# uC.net
KiCad netlist of a schematic drawn in Altium Designer
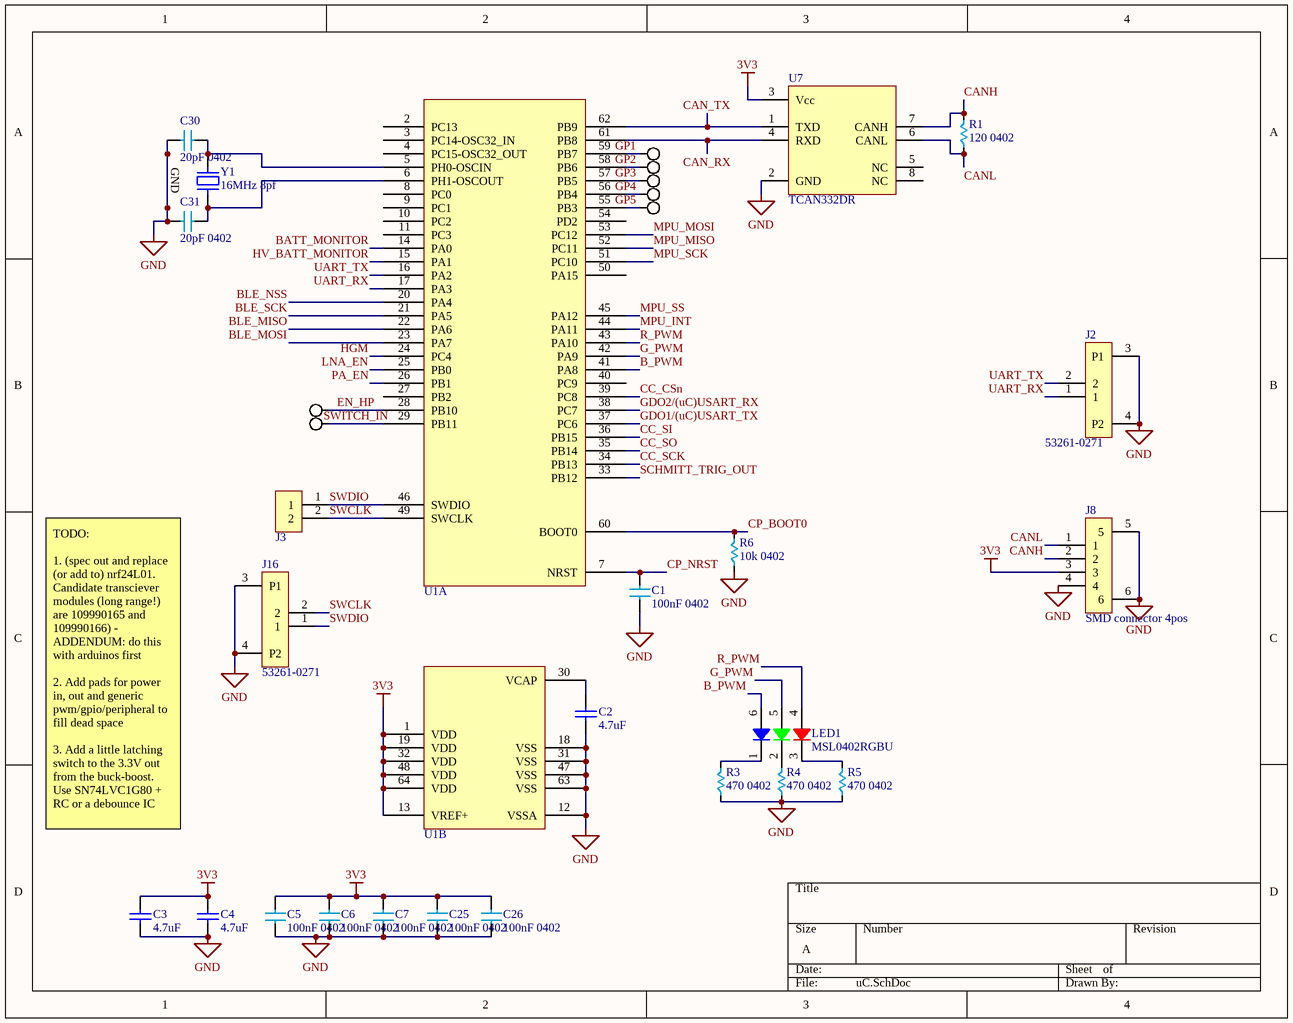
[diagram p0: uC.SchDoc]

(export (version "E")
  (design (tool "Eeschema 10.0.6"))
  (components
    (comp (ref "C1") (value "100nF 0402") (footprint "C0402") (libsource (lib "RLC") (part "C0402-100nF")))
    (comp (ref "C2")
      (value "4.7uF")
      (footprint "C0603")
      (description "4.7uF 0603")
      (fields
        (field (name "MANUFACTURER") "Samsung")
        (field (name "MANUFACTURER PART NUMBER") "CL05F104ZO5NNNC")
        (field (name "PUBLISHER") "Altium Limited")
      )
      (libsource (lib "robot-cortex") (part "C-4.7uF-0603"))
    )
    (comp (ref "C3")
      (value "4.7uF")
      (footprint "C0603")
      (description "4.7uF 0603")
      (fields
        (field (name "MANUFACTURER") "Samsung")
        (field (name "MANUFACTURER PART NUMBER") "CL05F104ZO5NNNC")
        (field (name "PUBLISHER") "Altium Limited")
      )
      (libsource (lib "robot-cortex") (part "C-4.7uF-0603"))
    )
    (comp (ref "C4")
      (value "4.7uF")
      (footprint "C0603")
      (description "4.7uF 0603")
      (fields
        (field (name "MANUFACTURER") "Samsung")
        (field (name "MANUFACTURER PART NUMBER") "CL05F104ZO5NNNC")
        (field (name "PUBLISHER") "Altium Limited")
      )
      (libsource (lib "robot-cortex") (part "C-4.7uF-0603"))
    )
    (comp (ref "C5") (value "100nF 0402") (footprint "C0402") (libsource (lib "RLC") (part "C0402-100nF")))
    (comp (ref "C6") (value "100nF 0402") (footprint "C0402") (libsource (lib "RLC") (part "C0402-100nF")))
    (comp (ref "C7") (value "100nF 0402") (footprint "C0402") (libsource (lib "RLC") (part "C0402-100nF")))
    (comp (ref "C25") (value "100nF 0402") (footprint "C0402") (libsource (lib "RLC") (part "C0402-100nF")))
    (comp (ref "C26") (value "100nF 0402") (footprint "C0402") (libsource (lib "RLC") (part "C0402-100nF")))
    (comp (ref "C30") (value "20pF 0402") (footprint "C0402") (libsource (lib "RLC") (part "C0402-20pF")))
    (comp (ref "C31") (value "20pF 0402") (footprint "C0402") (libsource (lib "RLC") (part "C0402-20pF")))
    (comp (ref "J2")
      (value "53261-0271")
      (footprint "0532610271")
      (description "Headers & Wire Housings 1.25MM HDR 2 CKT Right-Angle")
      (fields (field (name "MANUFACTURER") "Molex"))
      (libsource (lib "robot-cortex") (part "53261-0271"))
    )
    (comp (ref "J3")
      (value "Header 2")
      (footprint "DUAL_PADS")
      (libsource (lib "robot-cortex") (part "DUAL_PADS"))
    )
    (comp (ref "J5")
      (value "PAD-SINGLE")
      (footprint "PAD-SINGLE")
      (description "Single Thru Hole Pad")
      (libsource (lib "robot-cortex") (part "PAD-SINGLE"))
    )
    (comp (ref "J6")
      (value "PAD-SINGLE")
      (footprint "PAD-SINGLE")
      (description "Single Thru Hole Pad")
      (libsource (lib "robot-cortex") (part "PAD-SINGLE"))
    )
    (comp (ref "J8")
      (value "SMD connector 4pos")
      (footprint "0532610471")
      (description "Headers & Wire Housings 1.25MM HDR 4 CKT Right-Angle")
      (fields (field (name "MANUFACTURER") "Molex"))
      (libsource (lib "robot-cortex") (part "0532610471"))
    )
    (comp (ref "J9")
      (value "PAD-SINGLE")
      (footprint "PAD-SINGLE")
      (description "Single Thru Hole Pad")
      (libsource (lib "robot-cortex") (part "PAD-SINGLE"))
    )
    (comp (ref "J10")
      (value "PAD-SINGLE")
      (footprint "PAD-SINGLE")
      (description "Single Thru Hole Pad")
      (libsource (lib "robot-cortex") (part "PAD-SINGLE"))
    )
    (comp (ref "J11")
      (value "PAD-SINGLE")
      (footprint "PAD-SINGLE")
      (description "Single Thru Hole Pad")
      (libsource (lib "robot-cortex") (part "PAD-SINGLE"))
    )
    (comp (ref "J12")
      (value "PAD-SINGLE")
      (footprint "PAD-SINGLE")
      (description "Single Thru Hole Pad")
      (libsource (lib "robot-cortex") (part "PAD-SINGLE"))
    )
    (comp (ref "J13")
      (value "PAD-SINGLE")
      (footprint "PAD-SINGLE")
      (description "Single Thru Hole Pad")
      (libsource (lib "robot-cortex") (part "PAD-SINGLE"))
    )
    (comp (ref "J16")
      (value "53261-0271")
      (footprint "533980271")
      (description "Headers & Wire Housings 1.25MM HDR 2 CKT Right-Angle")
      (fields (field (name "MANUFACTURER") "Molex"))
      (libsource (lib "") (part "53261-0271_1"))
    )
    (comp (ref "LED1")
      (value "MSL0402RGBU")
      (footprint "MSL0402RGBU")
      (fields (field (name "MANUFACTURER") "Rohm") (field (name "MANUFACTURER PART NUMBER") "MSL0402RGBU1"))
      (libsource (lib "robot-cortex") (part "MSL0402RGBU"))
    )
    (comp (ref "R1")
      (value "120 0402")
      (footprint "R0402")
      (description "120 Ohm 0402")
      (libsource (lib "robot-cortex") (part "R-120-0402"))
    )
    (comp (ref "R3")
      (value "470 0402")
      (footprint "R0402")
      (fields
        (field (name "MANUFACTURER") "Yageo")
        (field (name "MANUFACTURER PART NUMBER") "RC0402JR-07470RL")
        (field (name "TOLERANCE") "5%")
      )
      (libsource (lib "robot-cortex") (part "R-470-0402"))
    )
    (comp (ref "R4")
      (value "470 0402")
      (footprint "R0402")
      (fields
        (field (name "MANUFACTURER") "Yageo")
        (field (name "MANUFACTURER PART NUMBER") "RC0402JR-07470RL")
        (field (name "TOLERANCE") "5%")
      )
      (libsource (lib "robot-cortex") (part "R-470-0402"))
    )
    (comp (ref "R5")
      (value "470 0402")
      (footprint "R0402")
      (fields
        (field (name "MANUFACTURER") "Yageo")
        (field (name "MANUFACTURER PART NUMBER") "RC0402JR-07470RL")
        (field (name "TOLERANCE") "5%")
      )
      (libsource (lib "robot-cortex") (part "R-470-0402"))
    )
    (comp (ref "R6") (value "10k 0402") (footprint "R0402") (libsource (lib "RLC") (part "R-10k-0402")))
    (comp (ref "U1")
      (value "STM32F730R8T6")
      (footprint "QFP-64")
      (libsource (lib "robot-cortex") (part "STM32F730R8T6"))
    )
    (comp (ref "U7")
      (value "TCAN332DR")
      (footprint "robot-cortex:SOIC8-D0008A")
      (fields (field (name "MANUFACTURER") "Texas Instruments"))
      (libsource (lib "robot-cortex") (part "TCAN332"))
    )
    (comp (ref "Y1")
      (value "16MHz 8pf")
      (footprint "robot-cortex:NDK NX3225GA")
      (description "SMT Crystal")
      (fields
        (field (name "MANUFACTURER") "NDK")
        (field (name "MANUFACTURER PART NUMBER") "NX3225SA-16.000000MHZ-T1")
      )
      (libsource (lib "robot-cortex") (part "NDK Crystal NX3225SA"))
    )
  )
  (nets
    (net (code "1") (name "/BATT_MONITOR") (class "Default")
      (node (ref "U1") (pin "14") (pinfunction "PA0_14") (pintype "passive"))
    )
    (net (code "2") (name "/BLE_MISO") (class "Default")
      (node (ref "U1") (pin "22") (pinfunction "PA6_22") (pintype "passive"))
    )
    (net (code "3") (name "/BLE_MOSI") (class "Default")
      (node (ref "U1") (pin "23") (pinfunction "PA7_23") (pintype "passive"))
    )
    (net (code "4") (name "/BLE_NSS") (class "Default")
      (node (ref "U1") (pin "20") (pinfunction "PA4_20") (pintype "passive"))
    )
    (net (code "5") (name "/BLE_SCK") (class "Default")
      (node (ref "U1") (pin "21") (pinfunction "PA5_21") (pintype "passive"))
    )
    (net (code "6") (name "/B_PWM") (class "Default")
      (node (ref "LED1") (pin "6") (pinfunction "6_6") (pintype "passive"))
      (node (ref "U1") (pin "41") (pinfunction "PA8_41") (pintype "passive"))
    )
    (net (code "7") (name "/CANH") (class "Default")
      (node (ref "J8") (pin "2") (pinfunction "2_2") (pintype "power_in"))
      (node (ref "R1") (pin "1") (pinfunction "1_1") (pintype "passive"))
      (node (ref "U7") (pin "7") (pinfunction "CANH_7") (pintype "power_in"))
    )
    (net (code "8") (name "/CANL") (class "Default")
      (node (ref "J8") (pin "1") (pinfunction "1_1") (pintype "power_in"))
      (node (ref "R1") (pin "2") (pinfunction "2_2") (pintype "passive"))
      (node (ref "U7") (pin "6") (pinfunction "CANL_6") (pintype "power_in"))
    )
    (net (code "9") (name "/CAN_RX") (class "Default")
      (node (ref "U1") (pin "61") (pinfunction "PB8_61") (pintype "passive"))
      (node (ref "U7") (pin "4") (pinfunction "RXD_4") (pintype "power_in"))
    )
    (net (code "10") (name "/CAN_TX") (class "Default")
      (node (ref "U1") (pin "62") (pinfunction "PB9_62") (pintype "passive"))
      (node (ref "U7") (pin "1") (pinfunction "TXD_1") (pintype "power_in"))
    )
    (net (code "11") (name "/CC_CSn") (class "Default")
      (node (ref "U1") (pin "39") (pinfunction "PC8_39") (pintype "passive"))
    )
    (net (code "12") (name "/CC_SCK") (class "Default")
      (node (ref "U1") (pin "34") (pinfunction "PB13_34") (pintype "passive"))
    )
    (net (code "13") (name "/CC_SI") (class "Default")
      (node (ref "U1") (pin "36") (pinfunction "PB15_36") (pintype "passive"))
    )
    (net (code "14") (name "/CC_SO") (class "Default")
      (node (ref "U1") (pin "35") (pinfunction "PB14_35") (pintype "passive"))
    )
    (net (code "15") (name "/CP_BOOT0") (class "Default")
      (node (ref "R6") (pin "1") (pinfunction "1_1") (pintype "passive"))
      (node (ref "U1") (pin "60") (pinfunction "BOOT0_60") (pintype "passive"))
    )
    (net (code "16") (name "/CP_NRST") (class "Default")
      (node (ref "C1") (pin "1") (pinfunction "1_1") (pintype "passive"))
      (node (ref "U1") (pin "7") (pinfunction "NRST_7") (pintype "passive"))
    )
    (net (code "17") (name "/EN_HP") (class "Default")
      (node (ref "J12") (pin "1") (pinfunction "1_1") (pintype "passive"))
      (node (ref "U1") (pin "28") (pinfunction "PB10_28") (pintype "passive"))
    )
    (net (code "18") (name "/GDO1{slash}(uC)USART_TX") (class "Default")
      (node (ref "U1") (pin "37") (pinfunction "PC6_37") (pintype "passive"))
    )
    (net (code "19") (name "/GDO2{slash}(uC)USART_RX") (class "Default")
      (node (ref "U1") (pin "38") (pinfunction "PC7_38") (pintype "passive"))
    )
    (net (code "20") (name "/GP1") (class "Default")
      (node (ref "J5") (pin "1") (pinfunction "1_1") (pintype "passive"))
      (node (ref "U1") (pin "59") (pinfunction "PB7_59") (pintype "passive"))
    )
    (net (code "21") (name "/GP2") (class "Default")
      (node (ref "J6") (pin "1") (pinfunction "1_1") (pintype "passive"))
      (node (ref "U1") (pin "58") (pinfunction "PB6_58") (pintype "passive"))
    )
    (net (code "22") (name "/GP3") (class "Default")
      (node (ref "J9") (pin "1") (pinfunction "1_1") (pintype "passive"))
      (node (ref "U1") (pin "57") (pinfunction "PB5_57") (pintype "passive"))
    )
    (net (code "23") (name "/GP4") (class "Default")
      (node (ref "J10") (pin "1") (pinfunction "1_1") (pintype "passive"))
      (node (ref "U1") (pin "56") (pinfunction "PB4_56") (pintype "passive"))
    )
    (net (code "24") (name "/GP5") (class "Default")
      (node (ref "J11") (pin "1") (pinfunction "1_1") (pintype "passive"))
      (node (ref "U1") (pin "55") (pinfunction "PB3_55") (pintype "passive"))
    )
    (net (code "25") (name "/G_PWM") (class "Default")
      (node (ref "LED1") (pin "5") (pinfunction "5_5") (pintype "passive"))
      (node (ref "U1") (pin "42") (pinfunction "PA9_42") (pintype "passive"))
    )
    (net (code "26") (name "/HGM") (class "Default")
      (node (ref "U1") (pin "24") (pinfunction "PC4_24") (pintype "passive"))
    )
    (net (code "27") (name "/HV_BATT_MONITOR") (class "Default")
      (node (ref "U1") (pin "15") (pinfunction "PA1_15") (pintype "passive"))
    )
    (net (code "28") (name "/LNA_EN") (class "Default")
      (node (ref "U1") (pin "25") (pinfunction "PB0_25") (pintype "passive"))
    )
    (net (code "29") (name "/MPU_INT") (class "Default")
      (node (ref "U1") (pin "44") (pinfunction "PA11_44") (pintype "passive"))
    )
    (net (code "30") (name "/MPU_MISO") (class "Default")
      (node (ref "U1") (pin "52") (pinfunction "PC11_52") (pintype "passive"))
    )
    (net (code "31") (name "/MPU_MOSI") (class "Default")
      (node (ref "U1") (pin "53") (pinfunction "PC12_53") (pintype "passive"))
    )
    (net (code "32") (name "/MPU_SCK") (class "Default")
      (node (ref "U1") (pin "51") (pinfunction "PC10_51") (pintype "passive"))
    )
    (net (code "33") (name "/MPU_SS") (class "Default")
      (node (ref "U1") (pin "45") (pinfunction "PA12_45") (pintype "passive"))
    )
    (net (code "34") (name "/PA_EN") (class "Default")
      (node (ref "U1") (pin "26") (pinfunction "PB1_26") (pintype "passive"))
    )
    (net (code "35") (name "/R_PWM") (class "Default")
      (node (ref "LED1") (pin "4") (pinfunction "4_4") (pintype "passive"))
      (node (ref "U1") (pin "43") (pinfunction "PA10_43") (pintype "passive"))
    )
    (net (code "36") (name "/SCHMITT_TRIG_OUT") (class "Default")
      (node (ref "U1") (pin "33") (pinfunction "PB12_33") (pintype "passive"))
    )
    (net (code "37") (name "/SWCLK") (class "Default")
      (node (ref "J16") (pin "2") (pinfunction "2_2") (pintype "power_in"))
      (node (ref "J3") (pin "2") (pinfunction "2_2") (pintype "power_in"))
      (node (ref "U1") (pin "49") (pinfunction "SWCLK_49") (pintype "passive"))
    )
    (net (code "38") (name "/SWDIO") (class "Default")
      (node (ref "J16") (pin "1") (pinfunction "1_1") (pintype "power_in"))
      (node (ref "J3") (pin "1") (pinfunction "1_1") (pintype "power_in"))
      (node (ref "U1") (pin "46") (pinfunction "SWDIO_46") (pintype "passive"))
    )
    (net (code "39") (name "/SWITCH_IN") (class "Default")
      (node (ref "J13") (pin "1") (pinfunction "1_1") (pintype "passive"))
      (node (ref "U1") (pin "29") (pinfunction "PB11_29") (pintype "passive"))
    )
    (net (code "40") (name "/UART_RX") (class "Default")
      (node (ref "J2") (pin "1") (pinfunction "1_1") (pintype "power_in"))
      (node (ref "U1") (pin "17") (pinfunction "PA3_17") (pintype "passive"))
    )
    (net (code "41") (name "/UART_TX") (class "Default")
      (node (ref "J2") (pin "2") (pinfunction "2_2") (pintype "power_in"))
      (node (ref "U1") (pin "16") (pinfunction "PA2_16") (pintype "passive"))
    )
    (net (code "42") (name "3V3") (class "Default")
      (node (ref "C25") (pin "1") (pinfunction "1_1") (pintype "passive"))
      (node (ref "C26") (pin "1") (pinfunction "1_1") (pintype "passive"))
      (node (ref "C3") (pin "2") (pinfunction "2_2") (pintype "passive"))
      (node (ref "C4") (pin "2") (pinfunction "2_2") (pintype "passive"))
      (node (ref "C5") (pin "1") (pinfunction "1_1") (pintype "passive"))
      (node (ref "C6") (pin "1") (pinfunction "1_1") (pintype "passive"))
      (node (ref "C7") (pin "1") (pinfunction "1_1") (pintype "passive"))
      (node (ref "J8") (pin "3") (pinfunction "3_3") (pintype "power_in"))
      (node (ref "U1") (pin "1") (pinfunction "VDD_1") (pintype "passive"))
      (node (ref "U1") (pin "13") (pinfunction "VREF+_13") (pintype "passive"))
      (node (ref "U1") (pin "19") (pinfunction "VDD_19") (pintype "passive"))
      (node (ref "U1") (pin "32") (pinfunction "VDD_32") (pintype "passive"))
      (node (ref "U1") (pin "48") (pinfunction "VDD_48") (pintype "passive"))
      (node (ref "U1") (pin "64") (pinfunction "VDD_64") (pintype "passive"))
      (node (ref "U7") (pin "3") (pinfunction "Vcc_3") (pintype "power_in"))
    )
    (net (code "43") (name "GND") (class "Default")
      (node (ref "C1") (pin "2") (pinfunction "2_2") (pintype "passive"))
      (node (ref "C2") (pin "1") (pinfunction "1_1") (pintype "passive"))
      (node (ref "C25") (pin "2") (pinfunction "2_2") (pintype "passive"))
      (node (ref "C26") (pin "2") (pinfunction "2_2") (pintype "passive"))
      (node (ref "C3") (pin "1") (pinfunction "1_1") (pintype "passive"))
      (node (ref "C30") (pin "2") (pinfunction "2_2") (pintype "passive"))
      (node (ref "C31") (pin "2") (pinfunction "2_2") (pintype "passive"))
      (node (ref "C4") (pin "1") (pinfunction "1_1") (pintype "passive"))
      (node (ref "C5") (pin "2") (pinfunction "2_2") (pintype "passive"))
      (node (ref "C6") (pin "2") (pinfunction "2_2") (pintype "passive"))
      (node (ref "C7") (pin "2") (pinfunction "2_2") (pintype "passive"))
      (node (ref "J16") (pin "3") (pinfunction "P1_3") (pintype "power_in"))
      (node (ref "J16") (pin "4") (pinfunction "P2_4") (pintype "power_in"))
      (node (ref "J2") (pin "3") (pinfunction "P1_3") (pintype "power_in"))
      (node (ref "J2") (pin "4") (pinfunction "P2_4") (pintype "power_in"))
      (node (ref "J8") (pin "4") (pinfunction "4_4") (pintype "power_in"))
      (node (ref "J8") (pin "5") (pinfunction "5_5") (pintype "power_in"))
      (node (ref "J8") (pin "6") (pinfunction "6_6") (pintype "power_in"))
      (node (ref "R3") (pin "2") (pinfunction "2_2") (pintype "passive"))
      (node (ref "R4") (pin "2") (pinfunction "2_2") (pintype "passive"))
      (node (ref "R5") (pin "2") (pinfunction "2_2") (pintype "passive"))
      (node (ref "R6") (pin "2") (pinfunction "2_2") (pintype "passive"))
      (node (ref "U1") (pin "12") (pinfunction "VSSA_12") (pintype "passive"))
      (node (ref "U1") (pin "18") (pinfunction "VSS_18") (pintype "passive"))
      (node (ref "U1") (pin "31") (pinfunction "VSS_31") (pintype "passive"))
      (node (ref "U1") (pin "47") (pinfunction "VSS_47") (pintype "passive"))
      (node (ref "U1") (pin "63") (pinfunction "VSS_63") (pintype "passive"))
      (node (ref "U7") (pin "2") (pinfunction "GND_2") (pintype "power_in"))
      (node (ref "Y1") (pin "2") (pinfunction "GND_2") (pintype "passive"))
      (node (ref "Y1") (pin "4") (pinfunction "GND_4") (pintype "passive"))
    )
    (net (code "44") (name "Net-(LED1-2-Pad3)") (class "Default")
      (node (ref "LED1") (pin "3") (pinfunction "2_3") (pintype "passive"))
      (node (ref "R5") (pin "1") (pinfunction "1_1") (pintype "passive"))
    )
    (net (code "45") (name "Net-(LED1-Pad1)") (class "Default")
      (node (ref "LED1") (pin "1") (pinfunction "1_1") (pintype "passive"))
      (node (ref "R3") (pin "1") (pinfunction "1_1") (pintype "passive"))
    )
    (net (code "46") (name "Net-(LED1-Pad2)") (class "Default")
      (node (ref "LED1") (pin "2") (pinfunction "2_2") (pintype "passive"))
      (node (ref "R4") (pin "1") (pinfunction "1_1") (pintype "passive"))
    )
    (net (code "47") (name "Net-(U1A-PH0-OSCIN)") (class "Default")
      (node (ref "C30") (pin "1") (pinfunction "1_1") (pintype "passive"))
      (node (ref "U1") (pin "5") (pinfunction "PH0-OSCIN_5") (pintype "passive"))
      (node (ref "Y1") (pin "1") (pinfunction "1_1") (pintype "passive"))
    )
    (net (code "48") (name "Net-(U1A-PH1-OSCOUT)") (class "Default")
      (node (ref "C31") (pin "1") (pinfunction "1_1") (pintype "passive"))
      (node (ref "U1") (pin "6") (pinfunction "PH1-OSCOUT_6") (pintype "passive"))
      (node (ref "Y1") (pin "3") (pinfunction "3_3") (pintype "passive"))
    )
    (net (code "49") (name "Net-(U1B-VCAP)") (class "Default")
      (node (ref "C2") (pin "2") (pinfunction "2_2") (pintype "passive"))
      (node (ref "U1") (pin "30") (pinfunction "VCAP_30") (pintype "passive"))
    )
    (net (code "50") (name "unconnected-(U1A-PA15-Pad50)") (class "Default")
      (node (ref "U1") (pin "50") (pinfunction "PA15_50") (pintype "passive"))
    )
    (net (code "51") (name "unconnected-(U1A-PB2-Pad27)") (class "Default")
      (node (ref "U1") (pin "27") (pinfunction "PB2_27") (pintype "passive"))
    )
    (net (code "52") (name "unconnected-(U1A-PC0-Pad8)") (class "Default")
      (node (ref "U1") (pin "8") (pinfunction "PC0_8") (pintype "passive"))
    )
    (net (code "53") (name "unconnected-(U1A-PC1-Pad9)") (class "Default")
      (node (ref "U1") (pin "9") (pinfunction "PC1_9") (pintype "passive"))
    )
    (net (code "54") (name "unconnected-(U1A-PC2-Pad10)") (class "Default")
      (node (ref "U1") (pin "10") (pinfunction "PC2_10") (pintype "passive"))
    )
    (net (code "55") (name "unconnected-(U1A-PC3-Pad11)") (class "Default")
      (node (ref "U1") (pin "11") (pinfunction "PC3_11") (pintype "passive"))
    )
    (net (code "56") (name "unconnected-(U1A-PC9-Pad40)") (class "Default")
      (node (ref "U1") (pin "40") (pinfunction "PC9_40") (pintype "passive"))
    )
    (net (code "57") (name "unconnected-(U1A-PC13-Pad2)") (class "Default")
      (node (ref "U1") (pin "2") (pinfunction "PC13_2") (pintype "passive"))
    )
    (net (code "58") (name "unconnected-(U1A-PC14-OSC32_IN-Pad3)") (class "Default")
      (node (ref "U1") (pin "3") (pinfunction "PC14-OSC32_IN_3") (pintype "passive"))
    )
    (net (code "59") (name "unconnected-(U1A-PC15-OSC32_OUT-Pad4)") (class "Default")
      (node (ref "U1") (pin "4") (pinfunction "PC15-OSC32_OUT_4") (pintype "passive"))
    )
    (net (code "60") (name "unconnected-(U1A-PD2-Pad54)") (class "Default")
      (node (ref "U1") (pin "54") (pinfunction "PD2_54") (pintype "passive"))
    )
    (net (code "61") (name "unconnected-(U7-NC-Pad5)") (class "Default")
      (node (ref "U7") (pin "5") (pinfunction "NC_5") (pintype "power_in"))
    )
    (net (code "62") (name "unconnected-(U7-NC-Pad8)") (class "Default")
      (node (ref "U7") (pin "8") (pinfunction "NC_8") (pintype "power_in"))
    )
  )
)
